# Option_AP6xxx.net
KiCad netlist of a schematic drawn in Altium Designer
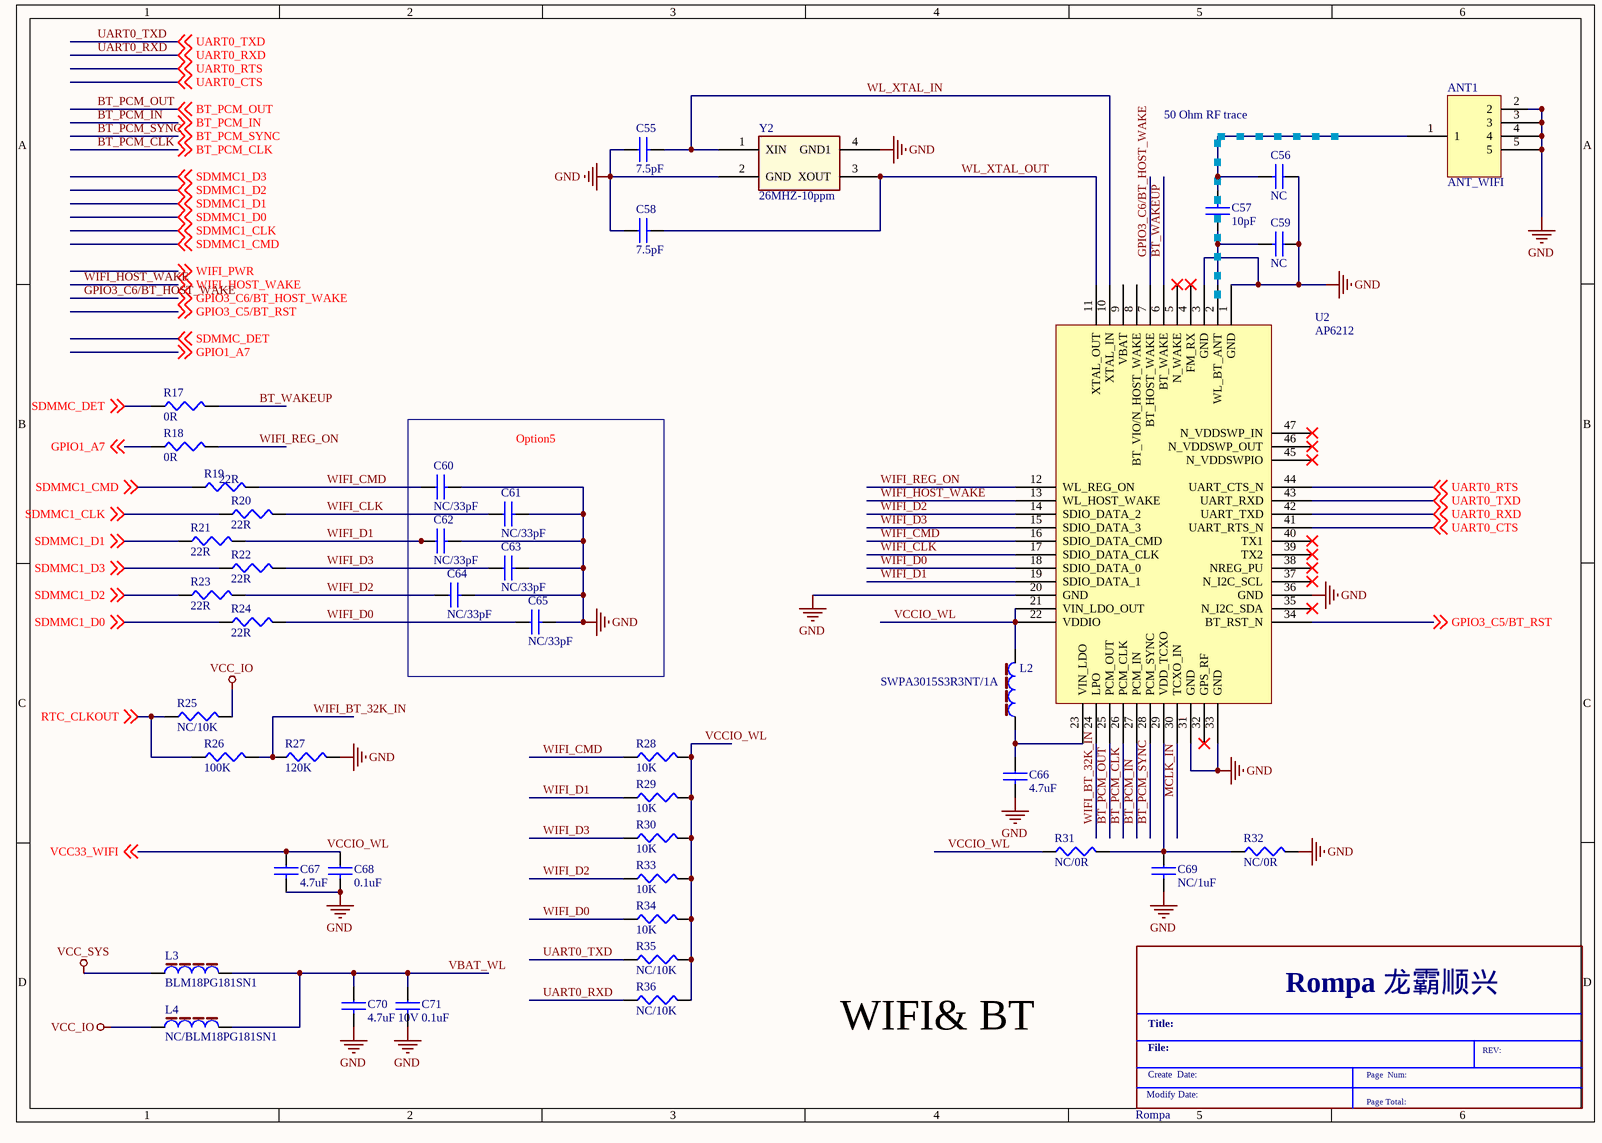
[diagram p0: Option_AP6xxx.SchDoc]

(export (version "E")
  (design (tool "Eeschema 10.0.6"))
  (components
    (comp (ref "ANT1") (value "ANT_WIFI") (libsource (lib "iguide_custom") (part "AP6xxx_ANT")))
    (comp (ref "C55")
      (value "7.5pF")
      (footprint "C0402")
      (libsource (lib "RK3128_BETA_V03_20151231_Library") (part "CAP NP"))
    )
    (comp (ref "C56")
      (value "NC")
      (footprint "C0402")
      (libsource (lib "RK3128_BETA_V03_20151231_Library") (part "CAP NP"))
    )
    (comp (ref "C57")
      (value "10pF")
      (footprint "C0402")
      (libsource (lib "RK3128_BETA_V03_20151231_Library") (part "CAP NP"))
    )
    (comp (ref "C58")
      (value "7.5pF")
      (footprint "C0402")
      (libsource (lib "RK3128_BETA_V03_20151231_Library") (part "CAP NP"))
    )
    (comp (ref "C59")
      (value "NC")
      (footprint "C0402")
      (libsource (lib "RK3128_BETA_V03_20151231_Library") (part "CAP NP"))
    )
    (comp (ref "C60")
      (value "NC/33pF")
      (footprint "C0402")
      (libsource (lib "RK3128_BETA_V03_20151231_Library") (part "CAP NP"))
    )
    (comp (ref "C61")
      (value "NC/33pF")
      (footprint "C0402")
      (libsource (lib "RK3128_BETA_V03_20151231_Library") (part "CAP NP"))
    )
    (comp (ref "C62")
      (value "NC/33pF")
      (footprint "C0402")
      (libsource (lib "RK3128_BETA_V03_20151231_Library") (part "CAP NP"))
    )
    (comp (ref "C63")
      (value "NC/33pF")
      (footprint "C0402")
      (libsource (lib "RK3128_BETA_V03_20151231_Library") (part "CAP NP"))
    )
    (comp (ref "C64")
      (value "NC/33pF")
      (footprint "C0402")
      (libsource (lib "RK3128_BETA_V03_20151231_Library") (part "CAP NP"))
    )
    (comp (ref "C65")
      (value "NC/33pF")
      (footprint "C0402")
      (libsource (lib "RK3128_BETA_V03_20151231_Library") (part "CAP NP"))
    )
    (comp (ref "C66")
      (value "4.7uF")
      (footprint "C0603")
      (description "10V")
      (libsource (lib "RK3128_BETA_V03_20151231_Library") (part "CAP NP_Dup1"))
    )
    (comp (ref "C67")
      (value "4.7uF")
      (footprint "C0603")
      (description "6.3V")
      (libsource (lib "RK3128_BETA_V03_20151231_Library") (part "CAP NP_Dup1"))
    )
    (comp (ref "C68")
      (value "0.1uF")
      (footprint "C0402")
      (libsource (lib "RK3128_BETA_V03_20151231_Library") (part "CAP NP"))
    )
    (comp (ref "C69")
      (value "NC/1uF")
      (footprint "C0402")
      (libsource (lib "RK3128_BETA_V03_20151231_Library") (part "CAP NP"))
    )
    (comp (ref "C70")
      (value "4.7uF 10V")
      (footprint "C0603")
      (libsource (lib "RK3128_BETA_V03_20151231_Library") (part "CAP NP_Dup1"))
    )
    (comp (ref "C71")
      (value "0.1uF")
      (footprint "C0402")
      (libsource (lib "RK3128_BETA_V03_20151231_Library") (part "CAP NP"))
    )
    (comp (ref "L2")
      (value "SWPA3015S3R3NT/1A")
      (description "IND_3x3  3.3uH/1A")
      (libsource (lib "") (part "INDUCTOR_2_1"))
    )
    (comp (ref "L3")
      (value "BLM18PG181SN1")
      (footprint "L0603")
      (libsource (lib "RK3128_BETA_V03_20151231_Library") (part "INDUCTOR_2"))
    )
    (comp (ref "L4")
      (value "NC/BLM18PG181SN1")
      (footprint "L0603")
      (libsource (lib "RK3128_BETA_V03_20151231_Library") (part "INDUCTOR_2"))
    )
    (comp (ref "R17")
      (value "0R")
      (footprint "R0402")
      (libsource (lib "RK3128_BETA_V03_20151231_Library") (part "RESISTOR"))
    )
    (comp (ref "R18")
      (value "0R")
      (footprint "R0402")
      (libsource (lib "RK3128_BETA_V03_20151231_Library") (part "RESISTOR"))
    )
    (comp (ref "R19")
      (value "22R")
      (footprint "R0402")
      (libsource (lib "RK3128_BETA_V03_20151231_Library") (part "RESISTOR"))
    )
    (comp (ref "R20")
      (value "22R")
      (footprint "R0402")
      (libsource (lib "RK3128_BETA_V03_20151231_Library") (part "RESISTOR"))
    )
    (comp (ref "R21")
      (value "22R")
      (footprint "R0402")
      (libsource (lib "RK3128_BETA_V03_20151231_Library") (part "RESISTOR"))
    )
    (comp (ref "R22")
      (value "22R")
      (footprint "R0402")
      (libsource (lib "RK3128_BETA_V03_20151231_Library") (part "RESISTOR"))
    )
    (comp (ref "R23")
      (value "22R")
      (footprint "R0402")
      (libsource (lib "RK3128_BETA_V03_20151231_Library") (part "RESISTOR"))
    )
    (comp (ref "R24")
      (value "22R")
      (footprint "R0402")
      (libsource (lib "RK3128_BETA_V03_20151231_Library") (part "RESISTOR"))
    )
    (comp (ref "R25")
      (value "NC/10K")
      (footprint "R0402")
      (libsource (lib "RK3128_BETA_V03_20151231_Library") (part "RESISTOR"))
    )
    (comp (ref "R26")
      (value "100K")
      (footprint "R0402")
      (libsource (lib "RK3128_BETA_V03_20151231_Library") (part "RESISTOR"))
    )
    (comp (ref "R27")
      (value "120K")
      (footprint "R0402")
      (libsource (lib "RK3128_BETA_V03_20151231_Library") (part "RESISTOR"))
    )
    (comp (ref "R28")
      (value "10K")
      (footprint "R0402")
      (libsource (lib "RK3128_BETA_V03_20151231_Library") (part "RESISTOR"))
    )
    (comp (ref "R29")
      (value "10K")
      (footprint "R0402")
      (libsource (lib "RK3128_BETA_V03_20151231_Library") (part "RESISTOR"))
    )
    (comp (ref "R30")
      (value "10K")
      (footprint "R0402")
      (libsource (lib "RK3128_BETA_V03_20151231_Library") (part "RESISTOR"))
    )
    (comp (ref "R31")
      (value "NC/0R")
      (footprint "R0402")
      (libsource (lib "RK3128_BETA_V03_20151231_Library") (part "RESISTOR"))
    )
    (comp (ref "R32")
      (value "NC/0R")
      (footprint "R0402")
      (libsource (lib "RK3128_BETA_V03_20151231_Library") (part "RESISTOR"))
    )
    (comp (ref "R33")
      (value "10K")
      (footprint "R0402")
      (libsource (lib "RK3128_BETA_V03_20151231_Library") (part "RESISTOR"))
    )
    (comp (ref "R34")
      (value "10K")
      (footprint "R0402")
      (libsource (lib "RK3128_BETA_V03_20151231_Library") (part "RESISTOR"))
    )
    (comp (ref "R35")
      (value "NC/10K")
      (footprint "R0402")
      (libsource (lib "RK3128_BETA_V03_20151231_Library") (part "RESISTOR"))
    )
    (comp (ref "R36")
      (value "NC/10K")
      (footprint "R0402")
      (libsource (lib "RK3128_BETA_V03_20151231_Library") (part "RESISTOR"))
    )
    (comp (ref "U2") (value "AP6212") (libsource (lib "iguide_custom") (part "AP6xxx")))
    (comp (ref "Y2")
      (value "26MHZ-10ppm")
      (footprint "CRY-3225")
      (libsource (lib "RK3128_BETA_V03_20151231_Library") (part "CRYSTAL-4_0"))
    )
  )
  (nets
    (net (code "1") (name "/BT_WAKEUP") (class "Default")
      (node (ref "R17") (pin "2") (pinfunction "2_2") (pintype "passive"))
      (node (ref "U2") (pin "6") (pinfunction "BT_WAKE_6") (pintype "passive"))
    )
    (net (code "2") (name "/MCLK_IN") (class "Default")
      (node (ref "U2") (pin "30") (pinfunction "TCXO_IN_30") (pintype "passive"))
    )
    (net (code "3") (name "/VBAT_WL") (class "Default")
      (node (ref "C70") (pin "1") (pinfunction "1_1") (pintype "passive"))
      (node (ref "C71") (pin "1") (pinfunction "1_1") (pintype "passive"))
      (node (ref "L3") (pin "2") (pinfunction "2_2") (pintype "passive"))
      (node (ref "L4") (pin "2") (pinfunction "2_2") (pintype "passive"))
    )
    (net (code "4") (name "/WIFI_BT_32K_IN") (class "Default")
      (node (ref "R26") (pin "2") (pinfunction "2_2") (pintype "passive"))
      (node (ref "R27") (pin "1") (pinfunction "1_1") (pintype "passive"))
      (node (ref "U2") (pin "24") (pinfunction "LPO_24") (pintype "passive"))
    )
    (net (code "5") (name "/WIFI_CLK") (class "Default")
      (node (ref "C61") (pin "1") (pinfunction "1_1") (pintype "passive"))
      (node (ref "R20") (pin "2") (pinfunction "2_2") (pintype "passive"))
      (node (ref "U2") (pin "17") (pinfunction "SDIO_DATA_CLK_17") (pintype "passive"))
    )
    (net (code "6") (name "/WIFI_CMD") (class "Default")
      (node (ref "C60") (pin "1") (pinfunction "1_1") (pintype "passive"))
      (node (ref "R19") (pin "2") (pinfunction "2_2") (pintype "passive"))
      (node (ref "R28") (pin "1") (pinfunction "1_1") (pintype "passive"))
      (node (ref "U2") (pin "16") (pinfunction "SDIO_DATA_CMD_16") (pintype "passive"))
    )
    (net (code "7") (name "/WIFI_D0") (class "Default")
      (node (ref "C65") (pin "1") (pinfunction "1_1") (pintype "passive"))
      (node (ref "R24") (pin "2") (pinfunction "2_2") (pintype "passive"))
      (node (ref "R34") (pin "1") (pinfunction "1_1") (pintype "passive"))
      (node (ref "U2") (pin "18") (pinfunction "SDIO_DATA_0_18") (pintype "passive"))
    )
    (net (code "8") (name "/WIFI_D1") (class "Default")
      (node (ref "C62") (pin "1") (pinfunction "1_1") (pintype "passive"))
      (node (ref "R21") (pin "2") (pinfunction "2_2") (pintype "passive"))
      (node (ref "R29") (pin "1") (pinfunction "1_1") (pintype "passive"))
      (node (ref "U2") (pin "19") (pinfunction "SDIO_DATA_1_19") (pintype "passive"))
    )
    (net (code "9") (name "/WIFI_D2") (class "Default")
      (node (ref "C64") (pin "1") (pinfunction "1_1") (pintype "passive"))
      (node (ref "R23") (pin "2") (pinfunction "2_2") (pintype "passive"))
      (node (ref "R33") (pin "1") (pinfunction "1_1") (pintype "passive"))
      (node (ref "U2") (pin "14") (pinfunction "SDIO_DATA_2_14") (pintype "passive"))
    )
    (net (code "10") (name "/WIFI_D3") (class "Default")
      (node (ref "C63") (pin "1") (pinfunction "1_1") (pintype "passive"))
      (node (ref "R22") (pin "2") (pinfunction "2_2") (pintype "passive"))
      (node (ref "R30") (pin "1") (pinfunction "1_1") (pintype "passive"))
      (node (ref "U2") (pin "15") (pinfunction "SDIO_DATA_3_15") (pintype "passive"))
    )
    (net (code "11") (name "/WIFI_REG_ON") (class "Default")
      (node (ref "R18") (pin "2") (pinfunction "2_2") (pintype "passive"))
      (node (ref "U2") (pin "12") (pinfunction "WL_REG_ON_12") (pintype "passive"))
    )
    (net (code "12") (name "/WL_XTAL_IN") (class "Default")
      (node (ref "C55") (pin "2") (pinfunction "2_2") (pintype "passive"))
      (node (ref "U2") (pin "10") (pinfunction "XTAL_IN_10") (pintype "passive"))
      (node (ref "Y2") (pin "1") (pinfunction "XIN_1") (pintype "passive"))
    )
    (net (code "13") (name "/WL_XTAL_OUT") (class "Default")
      (node (ref "C58") (pin "2") (pinfunction "2_2") (pintype "passive"))
      (node (ref "U2") (pin "11") (pinfunction "XTAL_OUT_11") (pintype "passive"))
      (node (ref "Y2") (pin "3") (pinfunction "XOUT_3") (pintype "passive"))
    )
    (net (code "14") (name "BT_PCM_CLK") (class "Default")
      (node (ref "U2") (pin "26") (pinfunction "PCM_CLK_26") (pintype "passive"))
    )
    (net (code "15") (name "BT_PCM_IN") (class "Default")
      (node (ref "U2") (pin "27") (pinfunction "PCM_IN_27") (pintype "passive"))
    )
    (net (code "16") (name "BT_PCM_OUT") (class "Default")
      (node (ref "U2") (pin "25") (pinfunction "PCM_OUT_25") (pintype "passive"))
    )
    (net (code "17") (name "BT_PCM_SYNC") (class "Default")
      (node (ref "U2") (pin "28") (pinfunction "PCM_SYNC_28") (pintype "passive"))
    )
    (net (code "18") (name "GND") (class "Default")
      (node (ref "ANT1") (pin "2") (pinfunction "2_2") (pintype "passive"))
      (node (ref "ANT1") (pin "3") (pinfunction "3_3") (pintype "passive"))
      (node (ref "ANT1") (pin "4") (pinfunction "4_4") (pintype "passive"))
      (node (ref "ANT1") (pin "5") (pinfunction "5_5") (pintype "passive"))
      (node (ref "C55") (pin "1") (pinfunction "1_1") (pintype "passive"))
      (node (ref "C56") (pin "1") (pinfunction "1_1") (pintype "passive"))
      (node (ref "C58") (pin "1") (pinfunction "1_1") (pintype "passive"))
      (node (ref "C59") (pin "1") (pinfunction "1_1") (pintype "passive"))
      (node (ref "C60") (pin "2") (pinfunction "2_2") (pintype "passive"))
      (node (ref "C61") (pin "2") (pinfunction "2_2") (pintype "passive"))
      (node (ref "C62") (pin "2") (pinfunction "2_2") (pintype "passive"))
      (node (ref "C63") (pin "2") (pinfunction "2_2") (pintype "passive"))
      (node (ref "C64") (pin "2") (pinfunction "2_2") (pintype "passive"))
      (node (ref "C65") (pin "2") (pinfunction "2_2") (pintype "passive"))
      (node (ref "C66") (pin "2") (pinfunction "2_2") (pintype "passive"))
      (node (ref "C67") (pin "2") (pinfunction "2_2") (pintype "passive"))
      (node (ref "C68") (pin "2") (pinfunction "2_2") (pintype "passive"))
      (node (ref "C69") (pin "2") (pinfunction "2_2") (pintype "passive"))
      (node (ref "C70") (pin "2") (pinfunction "2_2") (pintype "passive"))
      (node (ref "C71") (pin "2") (pinfunction "2_2") (pintype "passive"))
      (node (ref "R27") (pin "2") (pinfunction "2_2") (pintype "passive"))
      (node (ref "R32") (pin "2") (pinfunction "2_2") (pintype "passive"))
      (node (ref "U2") (pin "1") (pinfunction "GND_1") (pintype "passive"))
      (node (ref "U2") (pin "20") (pinfunction "GND_20") (pintype "passive"))
      (node (ref "U2") (pin "3") (pinfunction "GND_3") (pintype "passive"))
      (node (ref "U2") (pin "31") (pinfunction "GND_31") (pintype "passive"))
      (node (ref "U2") (pin "33") (pinfunction "GND_33") (pintype "passive"))
      (node (ref "U2") (pin "36") (pinfunction "GND_36") (pintype "passive"))
      (node (ref "Y2") (pin "2") (pinfunction "GND_2") (pintype "passive"))
      (node (ref "Y2") (pin "4") (pinfunction "GND1_4") (pintype "passive"))
    )
    (net (code "19") (name "GPIO1_A7") (class "Default")
      (node (ref "R18") (pin "1") (pinfunction "1_1") (pintype "passive"))
    )
    (net (code "20") (name "GPIO3_C5{slash}BT_RST") (class "Default")
      (node (ref "U2") (pin "34") (pinfunction "BT_RST_N_34") (pintype "passive"))
    )
    (net (code "21") (name "GPIO3_C6{slash}BT_HOST_WAKE") (class "Default")
      (node (ref "U2") (pin "7") (pinfunction "BT_HOST_WAKE_7") (pintype "passive"))
    )
    (net (code "22") (name "Net-(ANT1-Pad1)") (class "Default")
      (node (ref "ANT1") (pin "1") (pinfunction "1_1") (pintype "passive"))
      (node (ref "C56") (pin "2") (pinfunction "2_2") (pintype "passive"))
      (node (ref "C57") (pin "2") (pinfunction "2_2") (pintype "passive"))
    )
    (net (code "23") (name "Net-(U2-VDD_TCXO)") (class "Default")
      (node (ref "C69") (pin "1") (pinfunction "1_1") (pintype "passive"))
      (node (ref "R31") (pin "2") (pinfunction "2_2") (pintype "passive"))
      (node (ref "R32") (pin "1") (pinfunction "1_1") (pintype "passive"))
      (node (ref "U2") (pin "29") (pinfunction "VDD_TCXO_29") (pintype "passive"))
    )
    (net (code "24") (name "Net-(U2-VIN_LDO)") (class "Default")
      (node (ref "C66") (pin "1") (pinfunction "1_1") (pintype "passive"))
      (node (ref "L2") (pin "1") (pinfunction "1_1") (pintype "passive"))
      (node (ref "U2") (pin "23") (pinfunction "VIN_LDO_23") (pintype "passive"))
    )
    (net (code "25") (name "Net-(U2-WL_BT_ANT)") (class "Default")
      (node (ref "C57") (pin "1") (pinfunction "1_1") (pintype "passive"))
      (node (ref "C59") (pin "2") (pinfunction "2_2") (pintype "passive"))
      (node (ref "U2") (pin "2") (pinfunction "WL_BT_ANT_2") (pintype "passive"))
    )
    (net (code "26") (name "RTC_CLKOUT") (class "Default")
      (node (ref "R25") (pin "1") (pinfunction "1_1") (pintype "passive"))
      (node (ref "R26") (pin "1") (pinfunction "1_1") (pintype "passive"))
    )
    (net (code "27") (name "SDMMC1_CLK") (class "Default")
      (node (ref "R20") (pin "1") (pinfunction "1_1") (pintype "passive"))
    )
    (net (code "28") (name "SDMMC1_CMD") (class "Default")
      (node (ref "R19") (pin "1") (pinfunction "1_1") (pintype "passive"))
    )
    (net (code "29") (name "SDMMC1_D0") (class "Default")
      (node (ref "R24") (pin "1") (pinfunction "1_1") (pintype "passive"))
    )
    (net (code "30") (name "SDMMC1_D1") (class "Default")
      (node (ref "R21") (pin "1") (pinfunction "1_1") (pintype "passive"))
    )
    (net (code "31") (name "SDMMC1_D2") (class "Default")
      (node (ref "R23") (pin "1") (pinfunction "1_1") (pintype "passive"))
    )
    (net (code "32") (name "SDMMC1_D3") (class "Default")
      (node (ref "R22") (pin "1") (pinfunction "1_1") (pintype "passive"))
    )
    (net (code "33") (name "SDMMC_DET") (class "Default")
      (node (ref "R17") (pin "1") (pinfunction "1_1") (pintype "passive"))
    )
    (net (code "34") (name "UART0_CTS") (class "Default")
      (node (ref "U2") (pin "41") (pinfunction "UART_RTS_N_41") (pintype "passive"))
    )
    (net (code "35") (name "UART0_RTS") (class "Default")
      (node (ref "U2") (pin "44") (pinfunction "UART_CTS_N_44") (pintype "passive"))
    )
    (net (code "36") (name "UART0_RXD") (class "Default")
      (node (ref "R36") (pin "1") (pinfunction "1_1") (pintype "passive"))
      (node (ref "U2") (pin "42") (pinfunction "UART_TXD_42") (pintype "passive"))
    )
    (net (code "37") (name "UART0_TXD") (class "Default")
      (node (ref "R35") (pin "1") (pinfunction "1_1") (pintype "passive"))
      (node (ref "U2") (pin "43") (pinfunction "UART_RXD_43") (pintype "passive"))
    )
    (net (code "38") (name "VCC33_WIFI") (class "Default")
      (node (ref "C67") (pin "1") (pinfunction "1_1") (pintype "passive"))
      (node (ref "C68") (pin "1") (pinfunction "1_1") (pintype "passive"))
      (node (ref "L2") (pin "2") (pinfunction "2_2") (pintype "passive"))
      (node (ref "R28") (pin "2") (pinfunction "2_2") (pintype "passive"))
      (node (ref "R29") (pin "2") (pinfunction "2_2") (pintype "passive"))
      (node (ref "R30") (pin "2") (pinfunction "2_2") (pintype "passive"))
      (node (ref "R31") (pin "1") (pinfunction "1_1") (pintype "passive"))
      (node (ref "R33") (pin "2") (pinfunction "2_2") (pintype "passive"))
      (node (ref "R34") (pin "2") (pinfunction "2_2") (pintype "passive"))
      (node (ref "R35") (pin "2") (pinfunction "2_2") (pintype "passive"))
      (node (ref "R36") (pin "2") (pinfunction "2_2") (pintype "passive"))
      (node (ref "U2") (pin "21") (pinfunction "VIN_LDO_OUT_21") (pintype "passive"))
      (node (ref "U2") (pin "22") (pinfunction "VDDIO_22") (pintype "passive"))
    )
    (net (code "39") (name "VCC_IO") (class "Default")
      (node (ref "L4") (pin "1") (pinfunction "1_1") (pintype "passive"))
      (node (ref "R25") (pin "2") (pinfunction "2_2") (pintype "passive"))
    )
    (net (code "40") (name "VCC_SYS") (class "Default")
      (node (ref "L3") (pin "1") (pinfunction "1_1") (pintype "passive"))
    )
    (net (code "41") (name "WIFI_HOST_WAKE") (class "Default")
      (node (ref "U2") (pin "13") (pinfunction "WL_HOST_WAKE_13") (pintype "passive"))
    )
    (net (code "43") (name "unconnected-(U2-BT_VIO{slash}N_HOST_WAKE-Pad8)") (class "Default")
      (node (ref "U2") (pin "8") (pinfunction "BT_VIO/N_HOST_WAKE_8") (pintype "passive"))
    )
    (net (code "44") (name "unconnected-(U2-FM_RX-Pad4)") (class "Default")
      (node (ref "U2") (pin "4") (pinfunction "FM_RX_4") (pintype "passive+no_connect"))
    )
    (net (code "45") (name "unconnected-(U2-GPS_RF-Pad32)") (class "Default")
      (node (ref "U2") (pin "32") (pinfunction "GPS_RF_32") (pintype "passive+no_connect"))
    )
    (net (code "46") (name "unconnected-(U2-NREG_PU-Pad38)") (class "Default")
      (node (ref "U2") (pin "38") (pinfunction "NREG_PU_38") (pintype "passive+no_connect"))
    )
    (net (code "47") (name "unconnected-(U2-N_I2C_SCL-Pad37)") (class "Default")
      (node (ref "U2") (pin "37") (pinfunction "N_I2C_SCL_37") (pintype "passive+no_connect"))
    )
    (net (code "48") (name "unconnected-(U2-N_I2C_SDA-Pad35)") (class "Default")
      (node (ref "U2") (pin "35") (pinfunction "N_I2C_SDA_35") (pintype "passive+no_connect"))
    )
    (net (code "49") (name "unconnected-(U2-N_VDDSWPIO-Pad45)") (class "Default")
      (node (ref "U2") (pin "45") (pinfunction "N_VDDSWPIO_45") (pintype "passive+no_connect"))
    )
    (net (code "50") (name "unconnected-(U2-N_VDDSWP_IN-Pad47)") (class "Default")
      (node (ref "U2") (pin "47") (pinfunction "N_VDDSWP_IN_47") (pintype "passive+no_connect"))
    )
    (net (code "51") (name "unconnected-(U2-N_VDDSWP_OUT-Pad46)") (class "Default")
      (node (ref "U2") (pin "46") (pinfunction "N_VDDSWP_OUT_46") (pintype "passive+no_connect"))
    )
    (net (code "52") (name "unconnected-(U2-N_WAKE-Pad5)") (class "Default")
      (node (ref "U2") (pin "5") (pinfunction "N_WAKE_5") (pintype "passive+no_connect"))
    )
    (net (code "53") (name "unconnected-(U2-TX1-Pad40)") (class "Default")
      (node (ref "U2") (pin "40") (pinfunction "TX1_40") (pintype "passive+no_connect"))
    )
    (net (code "54") (name "unconnected-(U2-TX2-Pad39)") (class "Default")
      (node (ref "U2") (pin "39") (pinfunction "TX2_39") (pintype "passive+no_connect"))
    )
    (net (code "55") (name "unconnected-(U2-VBAT-Pad9)") (class "Default")
      (node (ref "U2") (pin "9") (pinfunction "VBAT_9") (pintype "passive"))
    )
  )
)
